# 190812-2.net
KiCad netlist of a schematic drawn in EAGLE
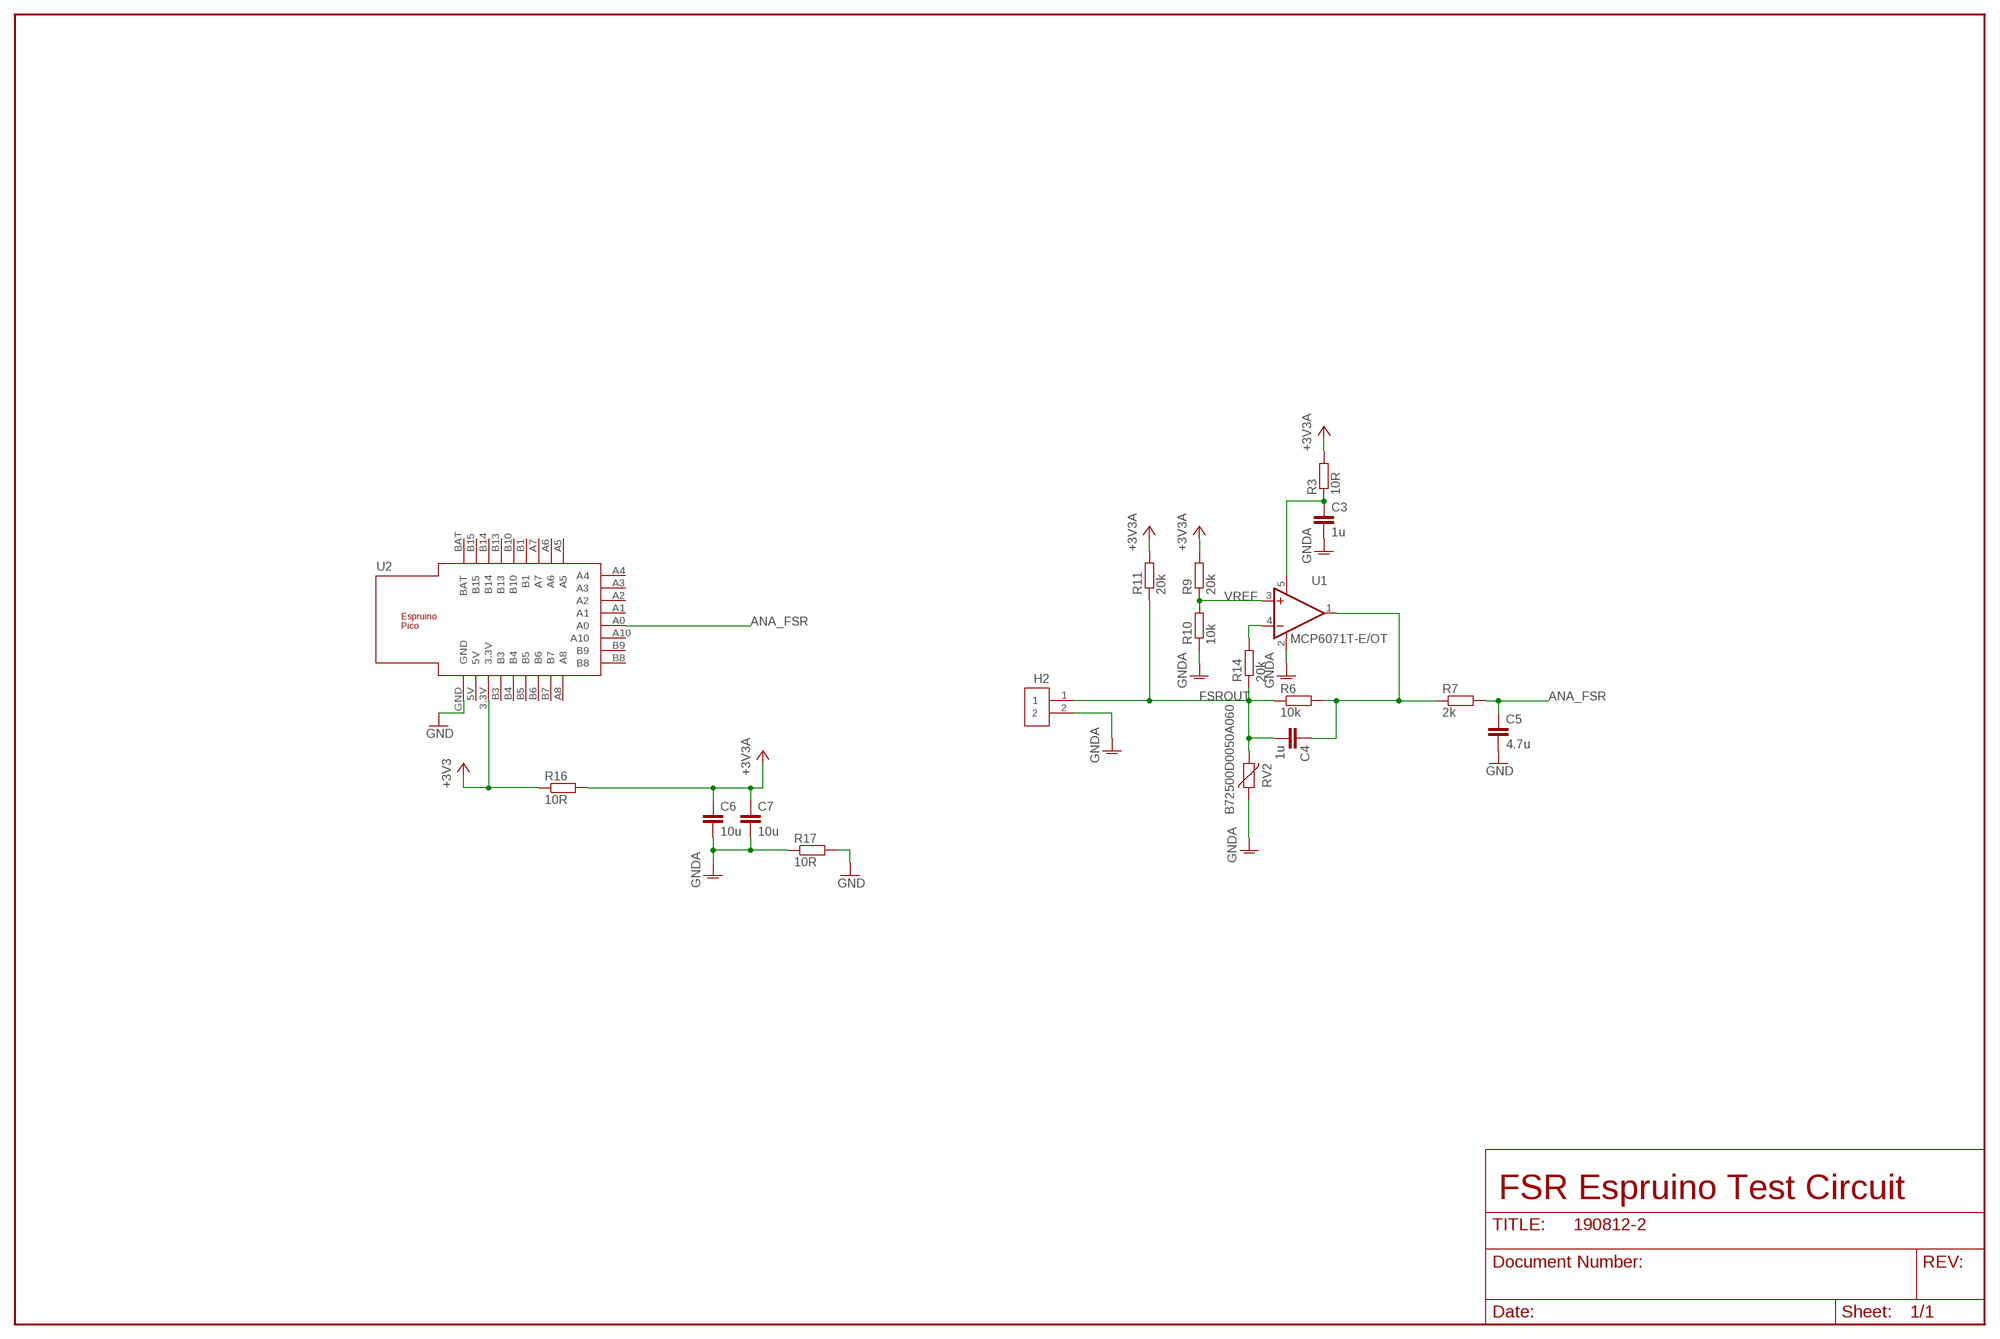
[diagram p0: schematic, sheet 1]

(export (version "E")
  (design (tool "Eeschema 10.0.6"))
  (components
    (comp (ref "C3")
      (value "1u")
      (footprint "eagle-import:C0603")
      (libsource (lib "eagle-import") (part "C-EUC0603"))
    )
    (comp (ref "C4")
      (value "1u")
      (footprint "eagle-import:C0805")
      (libsource (lib "eagle-import") (part "C-EUC0805"))
    )
    (comp (ref "C5")
      (value "4.7u")
      (footprint "eagle-import:C0805")
      (libsource (lib "eagle-import") (part "C-EUC0805"))
    )
    (comp (ref "C6")
      (value "10u")
      (footprint "eagle-import:C1206")
      (libsource (lib "eagle-import") (part "C-EUC1206"))
    )
    (comp (ref "C7")
      (value "10u")
      (footprint "eagle-import:C1206")
      (libsource (lib "eagle-import") (part "C-EUC1206"))
    )
    (comp (ref "H2")
      (value "FSR-CONNECTOR-RUGER")
      (footprint "eagle-import:1X02")
      (libsource (lib "eagle-import") (part "FSR-CONNECTOR-RUGER"))
    )
    (comp (ref "R3")
      (value "10R")
      (footprint "eagle-import:R0603")
      (libsource (lib "eagle-import") (part "R-EU_R0603"))
    )
    (comp (ref "R6")
      (value "10k")
      (footprint "eagle-import:R0603")
      (libsource (lib "eagle-import") (part "R-EU_R0603"))
    )
    (comp (ref "R7")
      (value "2k")
      (footprint "eagle-import:R0603")
      (libsource (lib "eagle-import") (part "R-EU_R0603"))
    )
    (comp (ref "R9")
      (value "20k")
      (footprint "eagle-import:R0603")
      (libsource (lib "eagle-import") (part "R-EU_R0603"))
    )
    (comp (ref "R10")
      (value "10k")
      (footprint "eagle-import:R0603")
      (libsource (lib "eagle-import") (part "R-EU_R0603"))
    )
    (comp (ref "R11")
      (value "20k")
      (footprint "eagle-import:R0603")
      (libsource (lib "eagle-import") (part "R-EU_R0603"))
    )
    (comp (ref "R14")
      (value "20k")
      (footprint "eagle-import:R0603")
      (libsource (lib "eagle-import") (part "R-EU_R0603"))
    )
    (comp (ref "R16")
      (value "10R")
      (footprint "eagle-import:R0603")
      (libsource (lib "eagle-import") (part "R-EU_R0603"))
    )
    (comp (ref "R17")
      (value "10R")
      (footprint "eagle-import:R0603")
      (libsource (lib "eagle-import") (part "R-EU_R0603"))
    )
    (comp (ref "RV2")
      (value "B72500D0050A060")
      (footprint "eagle-import:VARC1608X90")
      (libsource (lib "eagle-import") (part "B72500D0050A060"))
    )
    (comp (ref "U1")
      (value "MCP6071T-E/OT")
      (footprint "eagle-import:SOT95P270X145-5")
      (libsource (lib "eagle-import") (part "MCP6071T-E/OT"))
    )
    (comp (ref "U2")
      (value "ESPRUINO_PICO_SMDONLY")
      (footprint "eagle-import:ESPRUINO_PICO_SMDONLY")
      (libsource (lib "eagle-import") (part "ESPRUINO_PICO_SMDONLY"))
    )
  )
  (nets
    (net (code "1") (name "+3V3") (class "Default")
      (node (ref "R16") (pin "1") (pinfunction "1_1") (pintype "passive"))
      (node (ref "U2") (pin "3.3V") (pinfunction "3.3V_3.3V") (pintype "bidirectional"))
    )
    (net (code "2") (name "+3V3A") (class "Default")
      (node (ref "C6") (pin "1") (pinfunction "1_1") (pintype "passive"))
      (node (ref "C7") (pin "1") (pinfunction "1_1") (pintype "passive"))
      (node (ref "R11") (pin "2") (pinfunction "2_2") (pintype "passive"))
      (node (ref "R16") (pin "2") (pinfunction "2_2") (pintype "passive"))
      (node (ref "R3") (pin "2") (pinfunction "2_2") (pintype "passive"))
      (node (ref "R9") (pin "2") (pinfunction "2_2") (pintype "passive"))
    )
    (net (code "3") (name "/ANA_FSR") (class "Default")
      (node (ref "C5") (pin "1") (pinfunction "1_1") (pintype "passive"))
      (node (ref "R7") (pin "2") (pinfunction "2_2") (pintype "passive"))
      (node (ref "U2") (pin "A0") (pinfunction "A0_A0") (pintype "bidirectional"))
    )
    (net (code "4") (name "/FSROUT") (class "Default")
      (node (ref "C4") (pin "2") (pinfunction "2_2") (pintype "passive"))
      (node (ref "H2") (pin "1") (pinfunction "1_1") (pintype "passive"))
      (node (ref "R11") (pin "1") (pinfunction "1_1") (pintype "passive"))
      (node (ref "R14") (pin "1") (pinfunction "1_1") (pintype "passive"))
      (node (ref "R6") (pin "1") (pinfunction "1_1") (pintype "passive"))
      (node (ref "RV2") (pin "2") (pinfunction "2_2") (pintype "passive"))
    )
    (net (code "5") (name "/VREF") (class "Default")
      (node (ref "R10") (pin "2") (pinfunction "2_2") (pintype "passive"))
      (node (ref "R9") (pin "1") (pinfunction "1_1") (pintype "passive"))
      (node (ref "U1") (pin "3") (pinfunction "+IN_3") (pintype "input"))
    )
    (net (code "6") (name "GND") (class "Default")
      (node (ref "C5") (pin "2") (pinfunction "2_2") (pintype "passive"))
      (node (ref "R17") (pin "2") (pinfunction "2_2") (pintype "passive"))
      (node (ref "U2") (pin "GND") (pinfunction "GND_GND") (pintype "bidirectional"))
    )
    (net (code "7") (name "GNDA") (class "Default")
      (node (ref "C3") (pin "2") (pinfunction "2_2") (pintype "passive"))
      (node (ref "C6") (pin "2") (pinfunction "2_2") (pintype "passive"))
      (node (ref "C7") (pin "2") (pinfunction "2_2") (pintype "passive"))
      (node (ref "H2") (pin "2") (pinfunction "2_2") (pintype "passive"))
      (node (ref "R10") (pin "1") (pinfunction "1_1") (pintype "passive"))
      (node (ref "R17") (pin "1") (pinfunction "1_1") (pintype "passive"))
      (node (ref "RV2") (pin "1") (pinfunction "1_1") (pintype "passive"))
      (node (ref "U1") (pin "2") (pinfunction "V-_2") (pintype "power_in"))
    )
    (net (code "8") (name "Net-(U1--IN)") (class "Default")
      (node (ref "R14") (pin "2") (pinfunction "2_2") (pintype "passive"))
      (node (ref "U1") (pin "4") (pinfunction "-IN_4") (pintype "input"))
    )
    (net (code "9") (name "Net-(U1-OUT)") (class "Default")
      (node (ref "C4") (pin "1") (pinfunction "1_1") (pintype "passive"))
      (node (ref "R6") (pin "2") (pinfunction "2_2") (pintype "passive"))
      (node (ref "R7") (pin "1") (pinfunction "1_1") (pintype "passive"))
      (node (ref "U1") (pin "1") (pinfunction "OUT_1") (pintype "output"))
    )
    (net (code "10") (name "Net-(U1-V+)") (class "Default")
      (node (ref "C3") (pin "1") (pinfunction "1_1") (pintype "passive"))
      (node (ref "R3") (pin "1") (pinfunction "1_1") (pintype "passive"))
      (node (ref "U1") (pin "5") (pinfunction "V+_5") (pintype "power_in"))
    )
    (net (code "11") (name "unconnected-(U2-Pad5V)") (class "Default")
      (node (ref "U2") (pin "5V") (pinfunction "5V_5V") (pintype "bidirectional"))
    )
    (net (code "12") (name "unconnected-(U2-PadA1)") (class "Default")
      (node (ref "U2") (pin "A1") (pinfunction "A1_A1") (pintype "bidirectional"))
    )
    (net (code "13") (name "unconnected-(U2-PadA2)") (class "Default")
      (node (ref "U2") (pin "A2") (pinfunction "A2_A2") (pintype "bidirectional"))
    )
    (net (code "14") (name "unconnected-(U2-PadA3)") (class "Default")
      (node (ref "U2") (pin "A3") (pinfunction "A3_A3") (pintype "bidirectional"))
    )
    (net (code "15") (name "unconnected-(U2-PadA4)") (class "Default")
      (node (ref "U2") (pin "A4") (pinfunction "A4_A4") (pintype "bidirectional"))
    )
    (net (code "16") (name "unconnected-(U2-PadA5)") (class "Default")
      (node (ref "U2") (pin "A5") (pinfunction "A5_A5") (pintype "bidirectional"))
    )
    (net (code "17") (name "unconnected-(U2-PadA6)") (class "Default")
      (node (ref "U2") (pin "A6") (pinfunction "A6_A6") (pintype "bidirectional"))
    )
    (net (code "18") (name "unconnected-(U2-PadA7)") (class "Default")
      (node (ref "U2") (pin "A7") (pinfunction "A7_A7") (pintype "bidirectional"))
    )
    (net (code "19") (name "unconnected-(U2-PadA8)") (class "Default")
      (node (ref "U2") (pin "A8") (pinfunction "A8_A8") (pintype "bidirectional"))
    )
    (net (code "20") (name "unconnected-(U2-PadA10)") (class "Default")
      (node (ref "U2") (pin "A10") (pinfunction "A10_A10") (pintype "bidirectional"))
    )
    (net (code "21") (name "unconnected-(U2-PadB1)") (class "Default")
      (node (ref "U2") (pin "B1") (pinfunction "B1_B1") (pintype "bidirectional"))
    )
    (net (code "22") (name "unconnected-(U2-PadB3)") (class "Default")
      (node (ref "U2") (pin "B3") (pinfunction "B3_B3") (pintype "bidirectional"))
    )
    (net (code "23") (name "unconnected-(U2-PadB4)") (class "Default")
      (node (ref "U2") (pin "B4") (pinfunction "B4_B4") (pintype "bidirectional"))
    )
    (net (code "24") (name "unconnected-(U2-PadB5)") (class "Default")
      (node (ref "U2") (pin "B5") (pinfunction "B5_B5") (pintype "bidirectional"))
    )
    (net (code "25") (name "unconnected-(U2-PadB6)") (class "Default")
      (node (ref "U2") (pin "B6") (pinfunction "B6_B6") (pintype "bidirectional"))
    )
    (net (code "26") (name "unconnected-(U2-PadB7)") (class "Default")
      (node (ref "U2") (pin "B7") (pinfunction "B7_B7") (pintype "bidirectional"))
    )
    (net (code "27") (name "unconnected-(U2-PadB8)") (class "Default")
      (node (ref "U2") (pin "B8") (pinfunction "B8_B8") (pintype "bidirectional"))
    )
    (net (code "28") (name "unconnected-(U2-PadB9)") (class "Default")
      (node (ref "U2") (pin "B9") (pinfunction "B9_B9") (pintype "bidirectional"))
    )
    (net (code "29") (name "unconnected-(U2-PadB10)") (class "Default")
      (node (ref "U2") (pin "B10") (pinfunction "B10_B10") (pintype "bidirectional"))
    )
    (net (code "30") (name "unconnected-(U2-PadB13)") (class "Default")
      (node (ref "U2") (pin "B13") (pinfunction "B13_B13") (pintype "bidirectional"))
    )
    (net (code "31") (name "unconnected-(U2-PadB14)") (class "Default")
      (node (ref "U2") (pin "B14") (pinfunction "B14_B14") (pintype "bidirectional"))
    )
    (net (code "32") (name "unconnected-(U2-PadB15)") (class "Default")
      (node (ref "U2") (pin "B15") (pinfunction "B15_B15") (pintype "bidirectional"))
    )
    (net (code "33") (name "unconnected-(U2-PadBAT)") (class "Default")
      (node (ref "U2") (pin "BAT") (pinfunction "BAT_BAT") (pintype "bidirectional"))
    )
  )
)
